# Display50_Cape.net
KiCad netlist of a schematic drawn in EAGLE
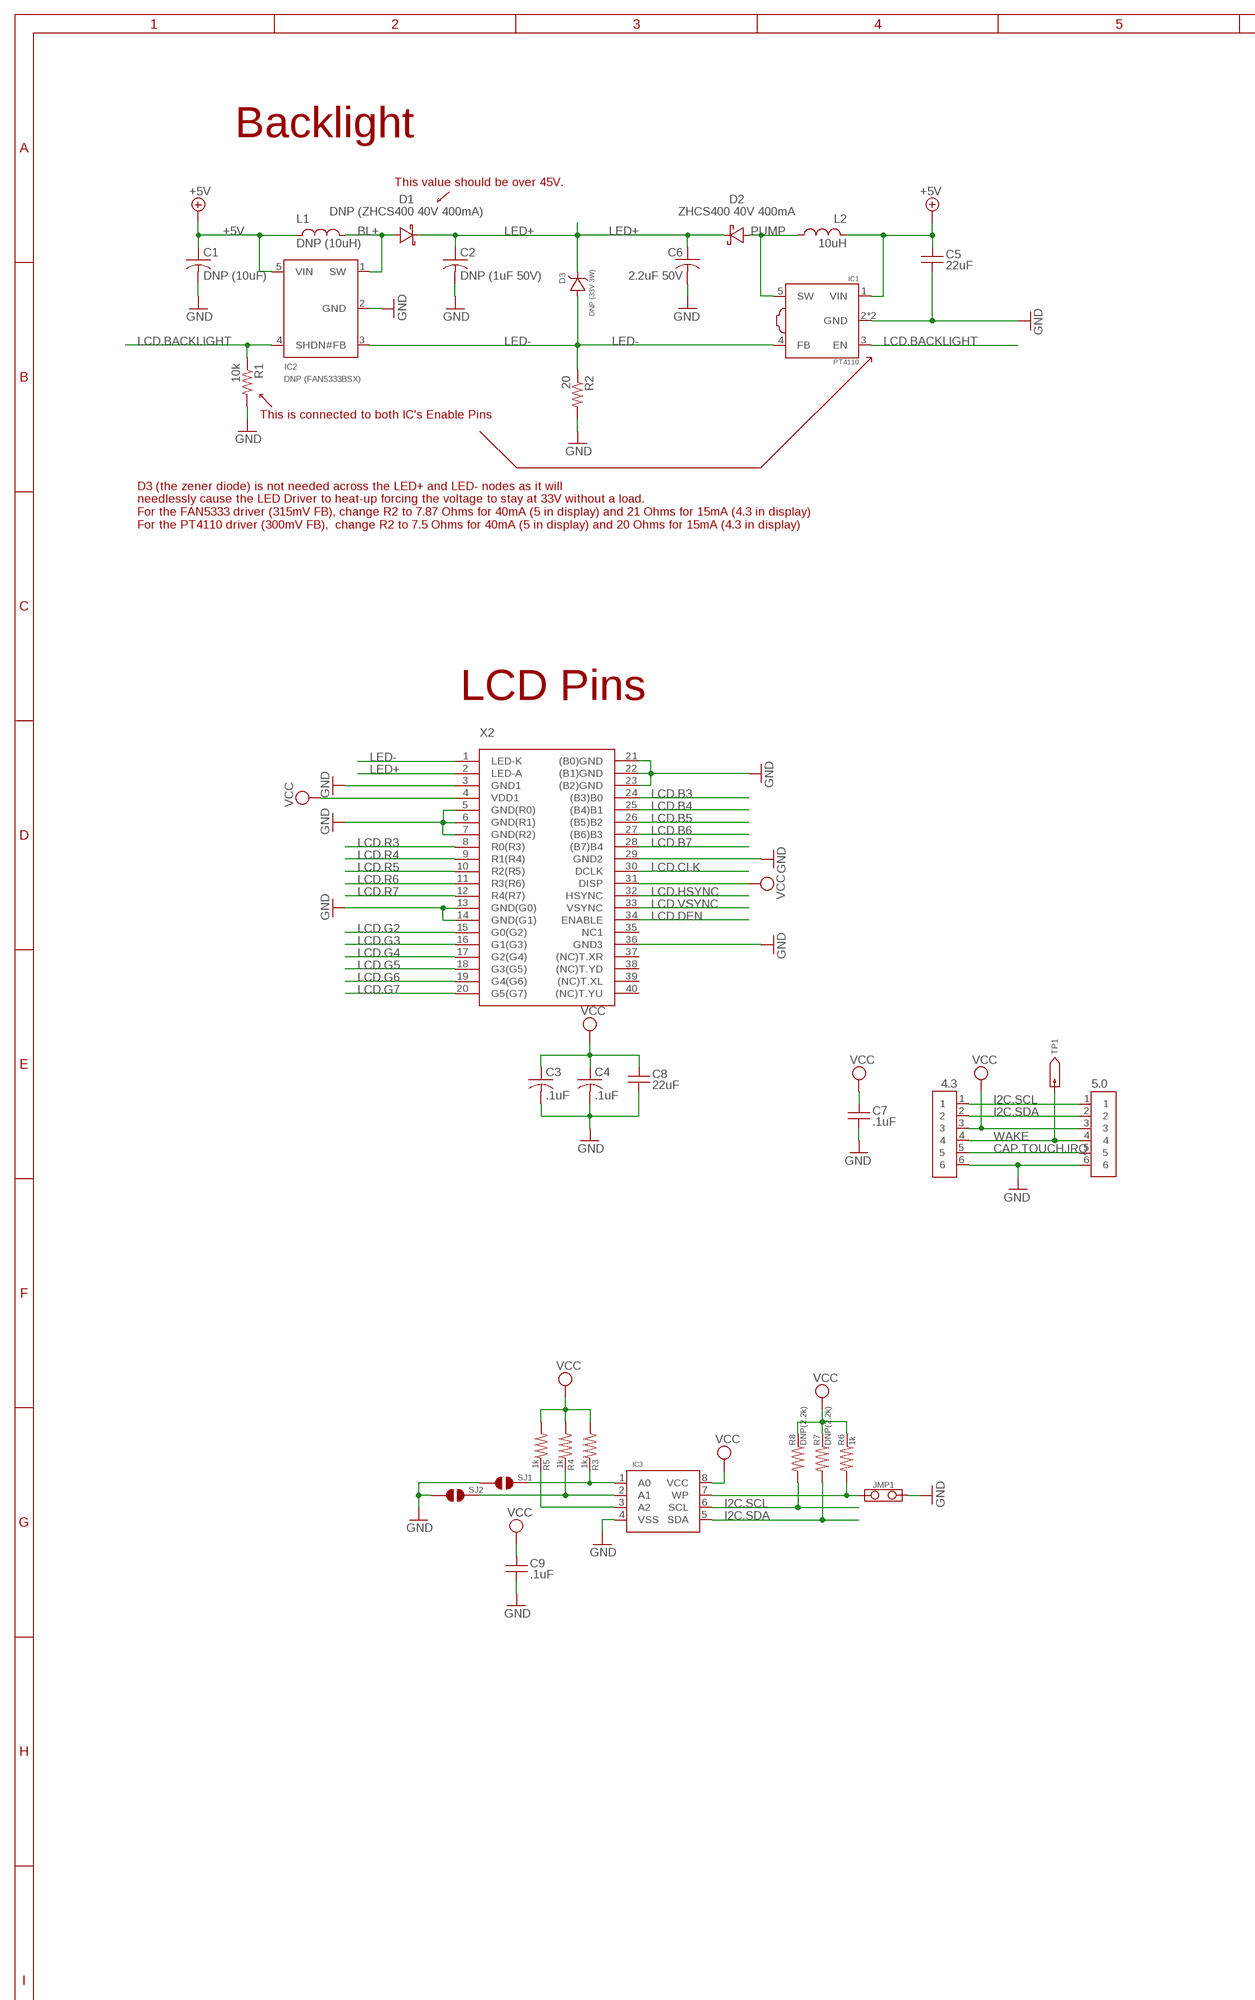
[diagram p0: schematic, sheet 1, part 1 of 2]
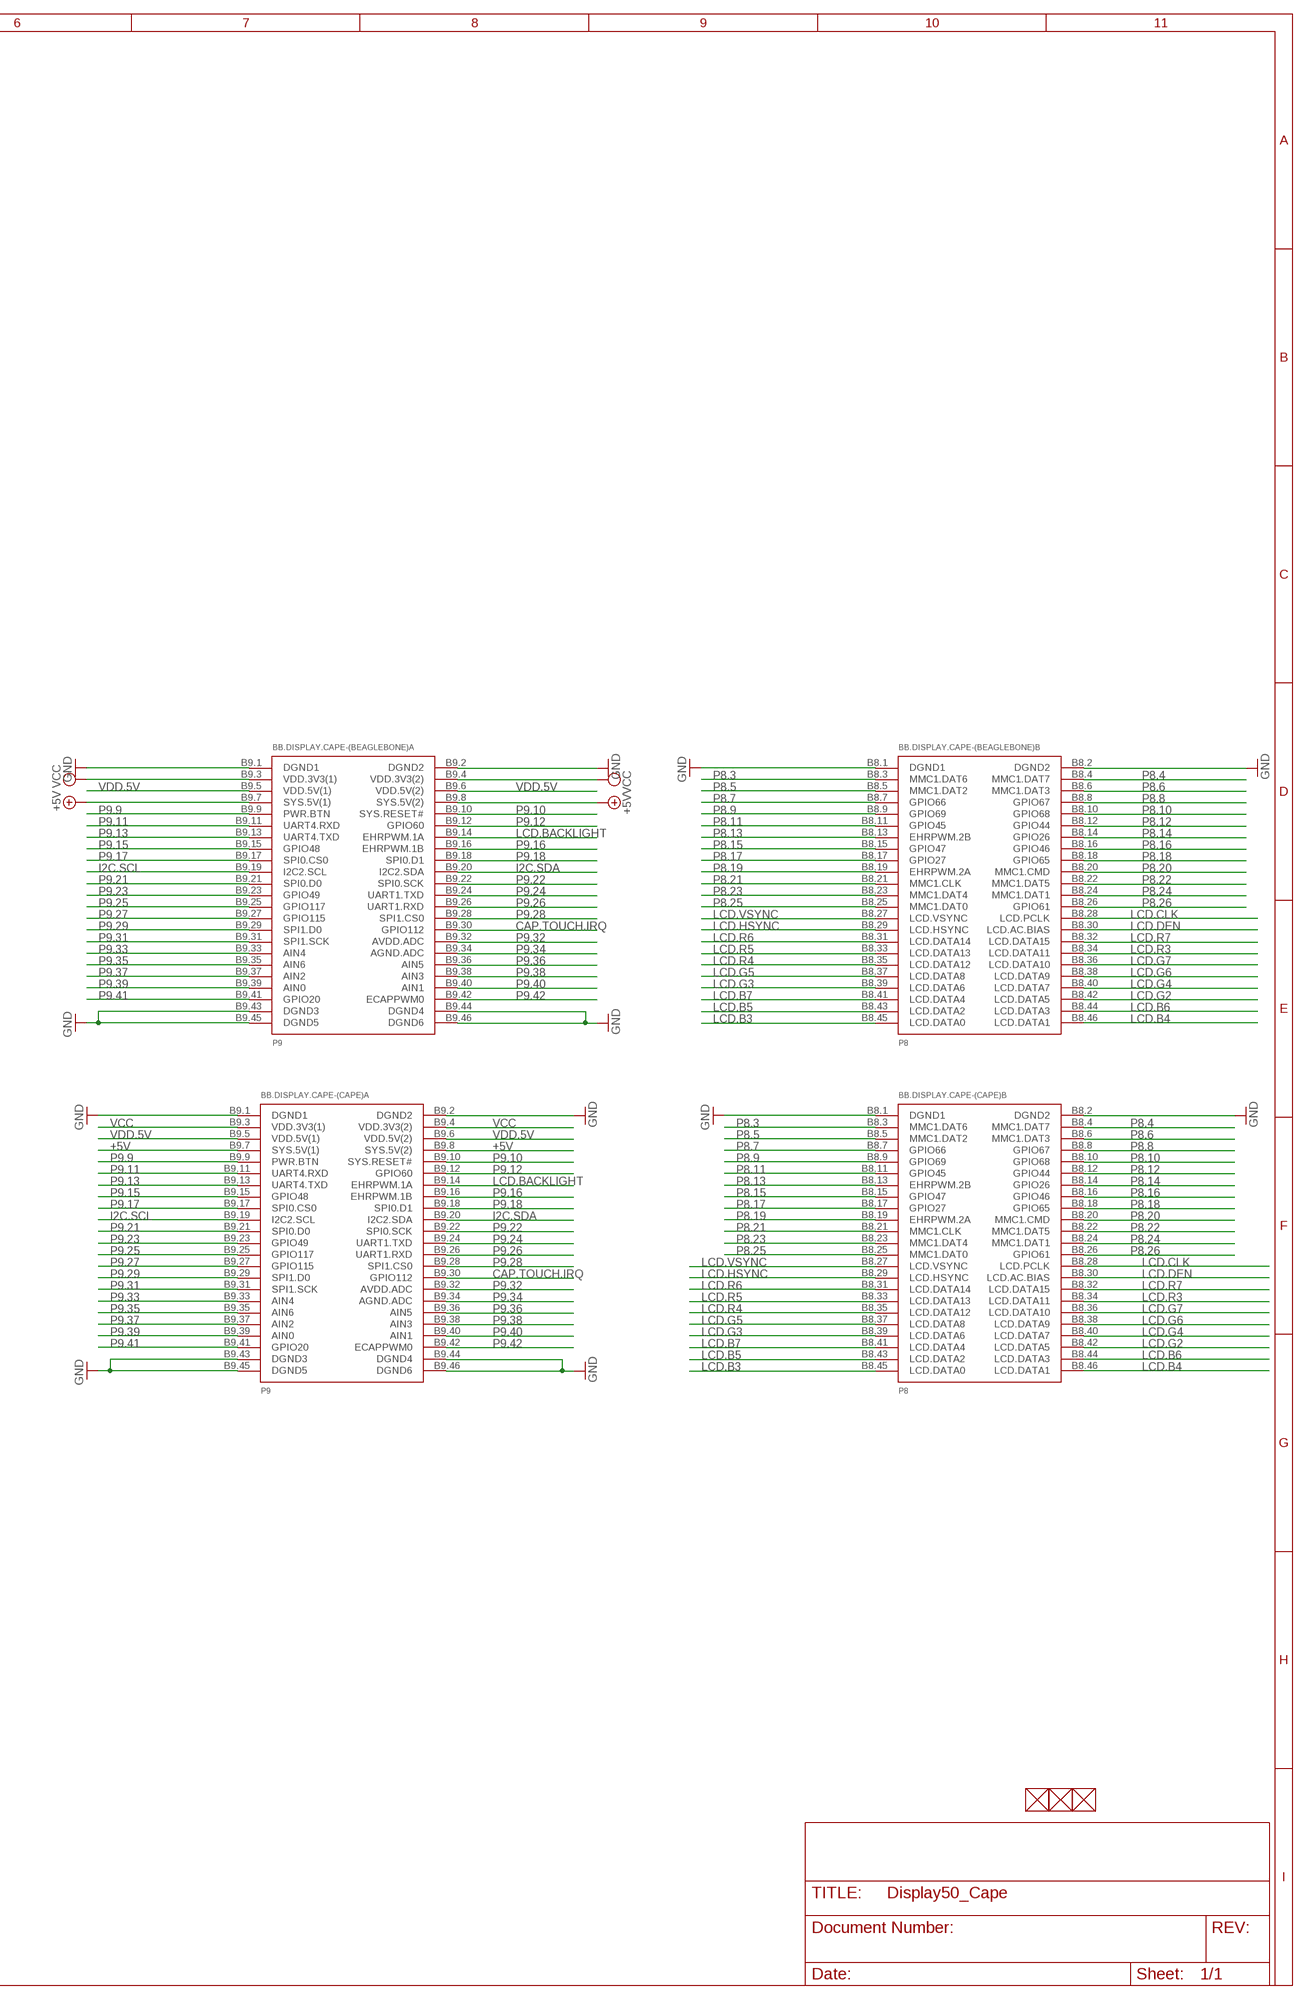
[diagram p1: schematic, sheet 1, part 2 of 2]

(export (version "E")
  (design (tool "Eeschema 10.0.6"))
  (components
    (comp (ref "4.3")
      (value "6-PIN-(0.5MM-PITCH)-FPC-CONNECTOR")
      (footprint "eagle-import:6-PIN-(0.5MM-PITCH)-FPC-CONNECTOR")
      (libsource (lib "eagle-import") (part "6-PIN-(0.5MM-PITCH)-FPC-CONNECTOR"))
    )
    (comp (ref "5.0")
      (value "6-PIN-(0.5MM-PITCH)-FPC-CONNECTOR")
      (footprint "eagle-import:6-PIN-(0.5MM-PITCH)-FPC-CONNECTOR")
      (libsource (lib "eagle-import") (part "6-PIN-(0.5MM-PITCH)-FPC-CONNECTOR"))
    )
    (comp (ref "BB.DISPLAY.CAPE-(BEAGLEBONE)")
      (value "BEAGLEBONE.CAPE.DISPLAY-X.BEAGLEBONE")
      (footprint "eagle-import:BEAGLEBONE.CAPE.DISPLAY-X.BEAGLEBONE")
      (libsource (lib "eagle-import") (part "BEAGLEBONE.CAPE.DISPLAY-X.BEAGLEBONE"))
    )
    (comp (ref "BB.DISPLAY.CAPE-(CAPE)")
      (value "BEAGLEBONE.CAPE.DISPLAY-X.CAPE")
      (footprint "eagle-import:BEAGLEBONE.CAPE.DISPLAY-X.CAPE")
      (libsource (lib "eagle-import") (part "BEAGLEBONE.CAPE.DISPLAY-X.CAPE"))
    )
    (comp (ref "C1")
      (value "DNP (10uF)")
      (footprint "eagle-import:C0603K")
      (libsource (lib "eagle-import") (part "C-USC0603K"))
    )
    (comp (ref "C2")
      (value "DNP (1uF 50V)")
      (footprint "eagle-import:C0805K")
      (libsource (lib "eagle-import") (part "C-USC0805K"))
    )
    (comp (ref "C3")
      (value ".1uF")
      (footprint "eagle-import:C0402K")
      (libsource (lib "eagle-import") (part "C-USC0402K"))
    )
    (comp (ref "C4")
      (value ".1uF")
      (footprint "eagle-import:C0402K")
      (libsource (lib "eagle-import") (part "C-USC0402K"))
    )
    (comp (ref "C5")
      (value "22uF")
      (footprint "eagle-import:0805")
      (libsource (lib "eagle-import") (part "CAPACITOR-(INCH)-0805"))
    )
    (comp (ref "C6")
      (value "2.2uF 50V")
      (footprint "eagle-import:C0805K")
      (libsource (lib "eagle-import") (part "C-USC0805K"))
    )
    (comp (ref "C7")
      (value ".1uF")
      (footprint "eagle-import:0402")
      (libsource (lib "eagle-import") (part "CAPACITOR-(INCH)-0402"))
    )
    (comp (ref "C8")
      (value "22uF")
      (footprint "eagle-import:0805")
      (libsource (lib "eagle-import") (part "CAPACITOR-(INCH)-0805"))
    )
    (comp (ref "C9")
      (value ".1uF")
      (footprint "eagle-import:0402")
      (libsource (lib "eagle-import") (part "CAPACITOR-(INCH)-0402"))
    )
    (comp (ref "D1")
      (value "DNP (ZHCS400 40V 400mA)")
      (footprint "eagle-import:SOD323(NXP)WAVE")
      (libsource (lib "eagle-import") (part "DIODE-SCHOTTKY-(NXP)-SOD323-(WAVE)"))
    )
    (comp (ref "D2")
      (value "ZHCS400 40V 400mA")
      (footprint "eagle-import:SOD323(NXP)WAVE")
      (libsource (lib "eagle-import") (part "DIODE-SCHOTTKY-(NXP)-SOD323-(WAVE)"))
    )
    (comp (ref "D3")
      (value "DNP (33V 3W)")
      (footprint "eagle-import:SMB(ON.SEMI)")
      (libsource (lib "eagle-import") (part "DIODE-ZENER-"))
    )
    (comp (ref "FUD1")
      (value "FIDUCIAL")
      (footprint "eagle-import:FIDUCIAL_40MIL")
      (libsource (lib "eagle-import") (part "FIDUCIAL"))
    )
    (comp (ref "FUD2")
      (value "FIDUCIAL")
      (footprint "eagle-import:FIDUCIAL_40MIL")
      (libsource (lib "eagle-import") (part "FIDUCIAL"))
    )
    (comp (ref "FUD3")
      (value "FIDUCIAL")
      (footprint "eagle-import:FIDUCIAL_40MIL")
      (libsource (lib "eagle-import") (part "FIDUCIAL"))
    )
    (comp (ref "IC1")
      (value "PT4110")
      (footprint "eagle-import:SOT89-5(DIODES)")
      (libsource (lib "eagle-import") (part "PT4110"))
    )
    (comp (ref "IC2")
      (value "DNP (FAN5333BSX)")
      (footprint "eagle-import:SOT23-5(FAIRCHILD)")
      (libsource (lib "eagle-import") (part "FAN533X"))
    )
    (comp (ref "IC3")
      (value "CAT24C32")
      (footprint "eagle-import:UDFN8,2X3(ON-SEMI)")
      (libsource (lib "eagle-import") (part "CAT24C32"))
    )
    (comp (ref "JMP1")
      (value "JUMPER-(X2)")
      (footprint "eagle-import:JUMPER-(X2)")
      (libsource (lib "eagle-import") (part "JUMPER-(X2)"))
    )
    (comp (ref "L1")
      (value "DNP (10uH)")
      (footprint "eagle-import:NRS(TAIYO.YUDEN)")
      (libsource (lib "eagle-import") (part "INDUCTOR-(TAIYO-YUDEN)-NRS5030"))
    )
    (comp (ref "L2")
      (value "10uH")
      (footprint "eagle-import:NRS(TAIYO.YUDEN)")
      (libsource (lib "eagle-import") (part "INDUCTOR-(TAIYO-YUDEN)-NRS5030"))
    )
    (comp (ref "R1")
      (value "10k")
      (footprint "eagle-import:R0603")
      (libsource (lib "eagle-import") (part "R-US_R0603"))
    )
    (comp (ref "R2")
      (value "20")
      (footprint "eagle-import:R0603")
      (libsource (lib "eagle-import") (part "R-US_R0603"))
    )
    (comp (ref "R3")
      (value "1k")
      (footprint "eagle-import:0402")
      (libsource (lib "eagle-import") (part "RESISTOR-(INCH)-0402"))
    )
    (comp (ref "R4")
      (value "1k")
      (footprint "eagle-import:0402")
      (libsource (lib "eagle-import") (part "RESISTOR-(INCH)-0402"))
    )
    (comp (ref "R5")
      (value "1k")
      (footprint "eagle-import:0402")
      (libsource (lib "eagle-import") (part "RESISTOR-(INCH)-0402"))
    )
    (comp (ref "R6")
      (value "1k")
      (footprint "eagle-import:0402")
      (libsource (lib "eagle-import") (part "RESISTOR-(INCH)-0402"))
    )
    (comp (ref "R7")
      (value "DNP(2.2k)")
      (footprint "eagle-import:0402")
      (libsource (lib "eagle-import") (part "RESISTOR-(INCH)-0402"))
    )
    (comp (ref "R8")
      (value "DNP(2.2k)")
      (footprint "eagle-import:0402")
      (libsource (lib "eagle-import") (part "RESISTOR-(INCH)-0402"))
    )
    (comp (ref "SJ1")
      (value "SOLDER.JOINT-(INCH)-0402")
      (footprint "eagle-import:SOLDER.JOINT(0402)")
      (libsource (lib "eagle-import") (part "SOLDER.JOINT-(INCH)-0402"))
    )
    (comp (ref "SJ2")
      (value "SOLDER.JOINT-(INCH)-0402")
      (footprint "eagle-import:SOLDER.JOINT(0402)")
      (libsource (lib "eagle-import") (part "SOLDER.JOINT-(INCH)-0402"))
    )
    (comp (ref "TP1")
      (value "TESTPAD/W_HOLE_1X1")
      (footprint "eagle-import:TESTPAD_W_HOLE_1X1")
      (libsource (lib "eagle-import") (part "TESTPAD/W_HOLE_1X1"))
    )
    (comp (ref "X2")
      (value "LCD-40PIN_FFC/FPC_0.5MM_PITCH")
      (footprint "eagle-import:KISD04-40_T1_E")
      (libsource (lib "eagle-import") (part "LCD-40PIN_FFC/FPC_0.5MM_PITCH"))
    )
  )
  (nets
    (net (code "1") (name "+5V") (class "Default")
      (node (ref "BB.DISPLAY.CAPE-(BEAGLEBONE)") (pin "B9.7") (pinfunction "SYS.5V(1)_B9.7") (pintype "bidirectional"))
      (node (ref "BB.DISPLAY.CAPE-(BEAGLEBONE)") (pin "B9.8") (pinfunction "SYS.5V(2)_B9.8") (pintype "bidirectional"))
      (node (ref "BB.DISPLAY.CAPE-(CAPE)") (pin "B9.7") (pinfunction "SYS.5V(1)_B9.7") (pintype "bidirectional"))
      (node (ref "BB.DISPLAY.CAPE-(CAPE)") (pin "B9.8") (pinfunction "SYS.5V(2)_B9.8") (pintype "bidirectional"))
      (node (ref "C1") (pin "1") (pinfunction "1_1") (pintype "passive"))
      (node (ref "C5") (pin "1") (pinfunction "1_1") (pintype "bidirectional"))
      (node (ref "IC1") (pin "1") (pinfunction "VIN_1") (pintype "bidirectional"))
      (node (ref "IC2") (pin "5") (pinfunction "VIN_5") (pintype "bidirectional"))
      (node (ref "L1") (pin "1") (pinfunction "1_1") (pintype "bidirectional"))
      (node (ref "L2") (pin "1") (pinfunction "1_1") (pintype "bidirectional"))
    )
    (net (code "2") (name "/BL+") (class "Default")
      (node (ref "D1") (pin "A") (pinfunction "ANODE_A") (pintype "bidirectional"))
      (node (ref "IC2") (pin "1") (pinfunction "SW_1") (pintype "bidirectional"))
      (node (ref "L1") (pin "2") (pinfunction "2_2") (pintype "bidirectional"))
    )
    (net (code "3") (name "/CAP.TOUCH.IRQ") (class "Default")
      (node (ref "4.3") (pin "5") (pinfunction "5_5") (pintype "bidirectional"))
      (node (ref "5.0") (pin "5") (pinfunction "5_5") (pintype "bidirectional"))
      (node (ref "BB.DISPLAY.CAPE-(BEAGLEBONE)") (pin "B9.30") (pinfunction "GPIO112_B9.30") (pintype "bidirectional"))
      (node (ref "BB.DISPLAY.CAPE-(CAPE)") (pin "B9.30") (pinfunction "GPIO112_B9.30") (pintype "bidirectional"))
    )
    (net (code "4") (name "/I2C.SCL") (class "Default")
      (node (ref "4.3") (pin "1") (pinfunction "1_1") (pintype "bidirectional"))
      (node (ref "5.0") (pin "1") (pinfunction "1_1") (pintype "bidirectional"))
      (node (ref "BB.DISPLAY.CAPE-(BEAGLEBONE)") (pin "B9.19") (pinfunction "I2C2.SCL_B9.19") (pintype "bidirectional"))
      (node (ref "BB.DISPLAY.CAPE-(CAPE)") (pin "B9.19") (pinfunction "I2C2.SCL_B9.19") (pintype "bidirectional"))
      (node (ref "IC3") (pin "6") (pinfunction "SCL_6") (pintype "bidirectional"))
      (node (ref "R8") (pin "1") (pinfunction "1_1") (pintype "bidirectional"))
    )
    (net (code "5") (name "/I2C.SDA") (class "Default")
      (node (ref "4.3") (pin "2") (pinfunction "2_2") (pintype "bidirectional"))
      (node (ref "5.0") (pin "2") (pinfunction "2_2") (pintype "bidirectional"))
      (node (ref "BB.DISPLAY.CAPE-(BEAGLEBONE)") (pin "B9.20") (pinfunction "I2C2.SDA_B9.20") (pintype "bidirectional"))
      (node (ref "BB.DISPLAY.CAPE-(CAPE)") (pin "B9.20") (pinfunction "I2C2.SDA_B9.20") (pintype "bidirectional"))
      (node (ref "IC3") (pin "5") (pinfunction "SDA_5") (pintype "bidirectional"))
      (node (ref "R7") (pin "1") (pinfunction "1_1") (pintype "bidirectional"))
    )
    (net (code "6") (name "/LCD.B3") (class "Default")
      (node (ref "BB.DISPLAY.CAPE-(BEAGLEBONE)") (pin "B8.45") (pinfunction "LCD.DATA0_B8.45") (pintype "bidirectional"))
      (node (ref "BB.DISPLAY.CAPE-(CAPE)") (pin "B8.45") (pinfunction "LCD.DATA0_B8.45") (pintype "bidirectional"))
      (node (ref "X2") (pin "24") (pinfunction "(B3)B0_24") (pintype "bidirectional"))
    )
    (net (code "7") (name "/LCD.B4") (class "Default")
      (node (ref "BB.DISPLAY.CAPE-(BEAGLEBONE)") (pin "B8.46") (pinfunction "LCD.DATA1_B8.46") (pintype "bidirectional"))
      (node (ref "BB.DISPLAY.CAPE-(CAPE)") (pin "B8.46") (pinfunction "LCD.DATA1_B8.46") (pintype "bidirectional"))
      (node (ref "X2") (pin "25") (pinfunction "(B4)B1_25") (pintype "bidirectional"))
    )
    (net (code "8") (name "/LCD.B5") (class "Default")
      (node (ref "BB.DISPLAY.CAPE-(BEAGLEBONE)") (pin "B8.43") (pinfunction "LCD.DATA2_B8.43") (pintype "bidirectional"))
      (node (ref "BB.DISPLAY.CAPE-(CAPE)") (pin "B8.43") (pinfunction "LCD.DATA2_B8.43") (pintype "bidirectional"))
      (node (ref "X2") (pin "26") (pinfunction "(B5)B2_26") (pintype "bidirectional"))
    )
    (net (code "9") (name "/LCD.B6") (class "Default")
      (node (ref "BB.DISPLAY.CAPE-(BEAGLEBONE)") (pin "B8.44") (pinfunction "LCD.DATA3_B8.44") (pintype "bidirectional"))
      (node (ref "BB.DISPLAY.CAPE-(CAPE)") (pin "B8.44") (pinfunction "LCD.DATA3_B8.44") (pintype "bidirectional"))
      (node (ref "X2") (pin "27") (pinfunction "(B6)B3_27") (pintype "bidirectional"))
    )
    (net (code "10") (name "/LCD.B7") (class "Default")
      (node (ref "BB.DISPLAY.CAPE-(BEAGLEBONE)") (pin "B8.41") (pinfunction "LCD.DATA4_B8.41") (pintype "bidirectional"))
      (node (ref "BB.DISPLAY.CAPE-(CAPE)") (pin "B8.41") (pinfunction "LCD.DATA4_B8.41") (pintype "bidirectional"))
      (node (ref "X2") (pin "28") (pinfunction "(B7)B4_28") (pintype "bidirectional"))
    )
    (net (code "11") (name "/LCD.BACKLIGHT") (class "Default")
      (node (ref "BB.DISPLAY.CAPE-(BEAGLEBONE)") (pin "B9.14") (pinfunction "EHRPWM.1A_B9.14") (pintype "bidirectional"))
      (node (ref "BB.DISPLAY.CAPE-(CAPE)") (pin "B9.14") (pinfunction "EHRPWM.1A_B9.14") (pintype "bidirectional"))
      (node (ref "IC1") (pin "3") (pinfunction "EN_3") (pintype "bidirectional"))
      (node (ref "IC2") (pin "4") (pinfunction "SHDN#_4") (pintype "bidirectional"))
      (node (ref "R1") (pin "1") (pinfunction "1_1") (pintype "passive"))
    )
    (net (code "12") (name "/LCD.CLK") (class "Default")
      (node (ref "BB.DISPLAY.CAPE-(BEAGLEBONE)") (pin "B8.28") (pinfunction "LCD.PCLK_B8.28") (pintype "bidirectional"))
      (node (ref "BB.DISPLAY.CAPE-(CAPE)") (pin "B8.28") (pinfunction "LCD.PCLK_B8.28") (pintype "bidirectional"))
      (node (ref "X2") (pin "30") (pinfunction "DCLK_30") (pintype "bidirectional"))
    )
    (net (code "13") (name "/LCD.DEN") (class "Default")
      (node (ref "BB.DISPLAY.CAPE-(BEAGLEBONE)") (pin "B8.30") (pinfunction "LCD.AC.BIAS_B8.30") (pintype "bidirectional"))
      (node (ref "BB.DISPLAY.CAPE-(CAPE)") (pin "B8.30") (pinfunction "LCD.AC.BIAS_B8.30") (pintype "bidirectional"))
      (node (ref "X2") (pin "34") (pinfunction "ENABLE_34") (pintype "bidirectional"))
    )
    (net (code "14") (name "/LCD.G2") (class "Default")
      (node (ref "BB.DISPLAY.CAPE-(BEAGLEBONE)") (pin "B8.42") (pinfunction "LCD.DATA5_B8.42") (pintype "bidirectional"))
      (node (ref "BB.DISPLAY.CAPE-(CAPE)") (pin "B8.42") (pinfunction "LCD.DATA5_B8.42") (pintype "bidirectional"))
      (node (ref "X2") (pin "15") (pinfunction "G0(G2)_15") (pintype "bidirectional"))
    )
    (net (code "15") (name "/LCD.G3") (class "Default")
      (node (ref "BB.DISPLAY.CAPE-(BEAGLEBONE)") (pin "B8.39") (pinfunction "LCD.DATA6_B8.39") (pintype "bidirectional"))
      (node (ref "BB.DISPLAY.CAPE-(CAPE)") (pin "B8.39") (pinfunction "LCD.DATA6_B8.39") (pintype "bidirectional"))
      (node (ref "X2") (pin "16") (pinfunction "G1(G3)_16") (pintype "bidirectional"))
    )
    (net (code "16") (name "/LCD.G4") (class "Default")
      (node (ref "BB.DISPLAY.CAPE-(BEAGLEBONE)") (pin "B8.40") (pinfunction "LCD.DATA7_B8.40") (pintype "bidirectional"))
      (node (ref "BB.DISPLAY.CAPE-(CAPE)") (pin "B8.40") (pinfunction "LCD.DATA7_B8.40") (pintype "bidirectional"))
      (node (ref "X2") (pin "17") (pinfunction "G2(G4)_17") (pintype "bidirectional"))
    )
    (net (code "17") (name "/LCD.G5") (class "Default")
      (node (ref "BB.DISPLAY.CAPE-(BEAGLEBONE)") (pin "B8.37") (pinfunction "LCD.DATA8_B8.37") (pintype "bidirectional"))
      (node (ref "BB.DISPLAY.CAPE-(CAPE)") (pin "B8.37") (pinfunction "LCD.DATA8_B8.37") (pintype "bidirectional"))
      (node (ref "X2") (pin "18") (pinfunction "G3(G5)_18") (pintype "bidirectional"))
    )
    (net (code "18") (name "/LCD.G6") (class "Default")
      (node (ref "BB.DISPLAY.CAPE-(BEAGLEBONE)") (pin "B8.38") (pinfunction "LCD.DATA9_B8.38") (pintype "bidirectional"))
      (node (ref "BB.DISPLAY.CAPE-(CAPE)") (pin "B8.38") (pinfunction "LCD.DATA9_B8.38") (pintype "bidirectional"))
      (node (ref "X2") (pin "19") (pinfunction "G4(G6)_19") (pintype "bidirectional"))
    )
    (net (code "19") (name "/LCD.G7") (class "Default")
      (node (ref "BB.DISPLAY.CAPE-(BEAGLEBONE)") (pin "B8.36") (pinfunction "LCD.DATA10_B8.36") (pintype "bidirectional"))
      (node (ref "BB.DISPLAY.CAPE-(CAPE)") (pin "B8.36") (pinfunction "LCD.DATA10_B8.36") (pintype "bidirectional"))
      (node (ref "X2") (pin "20") (pinfunction "G5(G7)_20") (pintype "bidirectional"))
    )
    (net (code "20") (name "/LCD.HSYNC") (class "Default")
      (node (ref "BB.DISPLAY.CAPE-(BEAGLEBONE)") (pin "B8.29") (pinfunction "LCD.HSYNC_B8.29") (pintype "bidirectional"))
      (node (ref "BB.DISPLAY.CAPE-(CAPE)") (pin "B8.29") (pinfunction "LCD.HSYNC_B8.29") (pintype "bidirectional"))
      (node (ref "X2") (pin "32") (pinfunction "HSYNC_32") (pintype "bidirectional"))
    )
    (net (code "21") (name "/LCD.R3") (class "Default")
      (node (ref "BB.DISPLAY.CAPE-(BEAGLEBONE)") (pin "B8.34") (pinfunction "LCD.DATA11_B8.34") (pintype "bidirectional"))
      (node (ref "BB.DISPLAY.CAPE-(CAPE)") (pin "B8.34") (pinfunction "LCD.DATA11_B8.34") (pintype "bidirectional"))
      (node (ref "X2") (pin "8") (pinfunction "R0(R3)_8") (pintype "bidirectional"))
    )
    (net (code "22") (name "/LCD.R4") (class "Default")
      (node (ref "BB.DISPLAY.CAPE-(BEAGLEBONE)") (pin "B8.35") (pinfunction "LCD.DATA12_B8.35") (pintype "bidirectional"))
      (node (ref "BB.DISPLAY.CAPE-(CAPE)") (pin "B8.35") (pinfunction "LCD.DATA12_B8.35") (pintype "bidirectional"))
      (node (ref "X2") (pin "9") (pinfunction "R1(R4)_9") (pintype "bidirectional"))
    )
    (net (code "23") (name "/LCD.R5") (class "Default")
      (node (ref "BB.DISPLAY.CAPE-(BEAGLEBONE)") (pin "B8.33") (pinfunction "LCD.DATA13_B8.33") (pintype "bidirectional"))
      (node (ref "BB.DISPLAY.CAPE-(CAPE)") (pin "B8.33") (pinfunction "LCD.DATA13_B8.33") (pintype "bidirectional"))
      (node (ref "X2") (pin "10") (pinfunction "R2(R5)_10") (pintype "bidirectional"))
    )
    (net (code "24") (name "/LCD.R6") (class "Default")
      (node (ref "BB.DISPLAY.CAPE-(BEAGLEBONE)") (pin "B8.31") (pinfunction "LCD.DATA14_B8.31") (pintype "bidirectional"))
      (node (ref "BB.DISPLAY.CAPE-(CAPE)") (pin "B8.31") (pinfunction "LCD.DATA14_B8.31") (pintype "bidirectional"))
      (node (ref "X2") (pin "11") (pinfunction "R3(R6)_11") (pintype "bidirectional"))
    )
    (net (code "25") (name "/LCD.R7") (class "Default")
      (node (ref "BB.DISPLAY.CAPE-(BEAGLEBONE)") (pin "B8.32") (pinfunction "LCD.DATA15_B8.32") (pintype "bidirectional"))
      (node (ref "BB.DISPLAY.CAPE-(CAPE)") (pin "B8.32") (pinfunction "LCD.DATA15_B8.32") (pintype "bidirectional"))
      (node (ref "X2") (pin "12") (pinfunction "R4(R7)_12") (pintype "bidirectional"))
    )
    (net (code "26") (name "/LCD.VSYNC") (class "Default")
      (node (ref "BB.DISPLAY.CAPE-(BEAGLEBONE)") (pin "B8.27") (pinfunction "LCD.VSYNC_B8.27") (pintype "bidirectional"))
      (node (ref "BB.DISPLAY.CAPE-(CAPE)") (pin "B8.27") (pinfunction "LCD.VSYNC_B8.27") (pintype "bidirectional"))
      (node (ref "X2") (pin "33") (pinfunction "VSYNC_33") (pintype "bidirectional"))
    )
    (net (code "27") (name "/LED+") (class "Default")
      (node (ref "C2") (pin "1") (pinfunction "1_1") (pintype "passive"))
      (node (ref "C6") (pin "1") (pinfunction "1_1") (pintype "passive"))
      (node (ref "D1") (pin "C") (pinfunction "CATHODE_C") (pintype "bidirectional"))
      (node (ref "D2") (pin "C") (pinfunction "CATHODE_C") (pintype "bidirectional"))
      (node (ref "D3") (pin "K") (pinfunction "K_K") (pintype "bidirectional"))
      (node (ref "X2") (pin "2") (pinfunction "LED-A_2") (pintype "bidirectional"))
    )
    (net (code "28") (name "/LED-") (class "Default")
      (node (ref "D3") (pin "A") (pinfunction "A_A") (pintype "bidirectional"))
      (node (ref "IC1") (pin "4") (pinfunction "FB_4") (pintype "bidirectional"))
      (node (ref "IC2") (pin "3") (pinfunction "FB_3") (pintype "bidirectional"))
      (node (ref "R2") (pin "1") (pinfunction "1_1") (pintype "passive"))
      (node (ref "X2") (pin "1") (pinfunction "LED-K_1") (pintype "bidirectional"))
    )
    (net (code "29") (name "/P8.3") (class "Default")
      (node (ref "BB.DISPLAY.CAPE-(BEAGLEBONE)") (pin "B8.3") (pinfunction "MMC1.DAT6_B8.3") (pintype "bidirectional"))
      (node (ref "BB.DISPLAY.CAPE-(CAPE)") (pin "B8.3") (pinfunction "MMC1.DAT6_B8.3") (pintype "bidirectional"))
    )
    (net (code "30") (name "/P8.4") (class "Default")
      (node (ref "BB.DISPLAY.CAPE-(BEAGLEBONE)") (pin "B8.4") (pinfunction "MMC1.DAT7_B8.4") (pintype "bidirectional"))
      (node (ref "BB.DISPLAY.CAPE-(CAPE)") (pin "B8.4") (pinfunction "MMC1.DAT7_B8.4") (pintype "bidirectional"))
    )
    (net (code "31") (name "/P8.5") (class "Default")
      (node (ref "BB.DISPLAY.CAPE-(BEAGLEBONE)") (pin "B8.5") (pinfunction "MMC1.DAT2_B8.5") (pintype "bidirectional"))
      (node (ref "BB.DISPLAY.CAPE-(CAPE)") (pin "B8.5") (pinfunction "MMC1.DAT2_B8.5") (pintype "bidirectional"))
    )
    (net (code "32") (name "/P8.6") (class "Default")
      (node (ref "BB.DISPLAY.CAPE-(BEAGLEBONE)") (pin "B8.6") (pinfunction "MMC1.DAT3_B8.6") (pintype "bidirectional"))
      (node (ref "BB.DISPLAY.CAPE-(CAPE)") (pin "B8.6") (pinfunction "MMC1.DAT3_B8.6") (pintype "bidirectional"))
    )
    (net (code "33") (name "/P8.7") (class "Default")
      (node (ref "BB.DISPLAY.CAPE-(BEAGLEBONE)") (pin "B8.7") (pinfunction "GPIO66_B8.7") (pintype "bidirectional"))
      (node (ref "BB.DISPLAY.CAPE-(CAPE)") (pin "B8.7") (pinfunction "GPIO66_B8.7") (pintype "bidirectional"))
    )
    (net (code "34") (name "/P8.8") (class "Default")
      (node (ref "BB.DISPLAY.CAPE-(BEAGLEBONE)") (pin "B8.8") (pinfunction "GPIO67_B8.8") (pintype "bidirectional"))
      (node (ref "BB.DISPLAY.CAPE-(CAPE)") (pin "B8.8") (pinfunction "GPIO67_B8.8") (pintype "bidirectional"))
    )
    (net (code "35") (name "/P8.9") (class "Default")
      (node (ref "BB.DISPLAY.CAPE-(BEAGLEBONE)") (pin "B8.9") (pinfunction "GPIO69_B8.9") (pintype "bidirectional"))
      (node (ref "BB.DISPLAY.CAPE-(CAPE)") (pin "B8.9") (pinfunction "GPIO69_B8.9") (pintype "bidirectional"))
    )
    (net (code "36") (name "/P8.10") (class "Default")
      (node (ref "BB.DISPLAY.CAPE-(BEAGLEBONE)") (pin "B8.10") (pinfunction "GPIO68_B8.10") (pintype "bidirectional"))
      (node (ref "BB.DISPLAY.CAPE-(CAPE)") (pin "B8.10") (pinfunction "GPIO68_B8.10") (pintype "bidirectional"))
    )
    (net (code "37") (name "/P8.11") (class "Default")
      (node (ref "BB.DISPLAY.CAPE-(BEAGLEBONE)") (pin "B8.11") (pinfunction "GPIO45_B8.11") (pintype "bidirectional"))
      (node (ref "BB.DISPLAY.CAPE-(CAPE)") (pin "B8.11") (pinfunction "GPIO45_B8.11") (pintype "bidirectional"))
    )
    (net (code "38") (name "/P8.12") (class "Default")
      (node (ref "BB.DISPLAY.CAPE-(BEAGLEBONE)") (pin "B8.12") (pinfunction "GPIO44_B8.12") (pintype "bidirectional"))
      (node (ref "BB.DISPLAY.CAPE-(CAPE)") (pin "B8.12") (pinfunction "GPIO44_B8.12") (pintype "bidirectional"))
    )
    (net (code "39") (name "/P8.13") (class "Default")
      (node (ref "BB.DISPLAY.CAPE-(BEAGLEBONE)") (pin "B8.13") (pinfunction "EHRPWM.2B_B8.13") (pintype "bidirectional"))
      (node (ref "BB.DISPLAY.CAPE-(CAPE)") (pin "B8.13") (pinfunction "EHRPWM.2B_B8.13") (pintype "bidirectional"))
    )
    (net (code "40") (name "/P8.14") (class "Default")
      (node (ref "BB.DISPLAY.CAPE-(BEAGLEBONE)") (pin "B8.14") (pinfunction "GPIO26_B8.14") (pintype "bidirectional"))
      (node (ref "BB.DISPLAY.CAPE-(CAPE)") (pin "B8.14") (pinfunction "GPIO26_B8.14") (pintype "bidirectional"))
    )
    (net (code "41") (name "/P8.15") (class "Default")
      (node (ref "BB.DISPLAY.CAPE-(BEAGLEBONE)") (pin "B8.15") (pinfunction "GPIO47_B8.15") (pintype "bidirectional"))
      (node (ref "BB.DISPLAY.CAPE-(CAPE)") (pin "B8.15") (pinfunction "GPIO47_B8.15") (pintype "bidirectional"))
    )
    (net (code "42") (name "/P8.16") (class "Default")
      (node (ref "BB.DISPLAY.CAPE-(BEAGLEBONE)") (pin "B8.16") (pinfunction "GPIO46_B8.16") (pintype "bidirectional"))
      (node (ref "BB.DISPLAY.CAPE-(CAPE)") (pin "B8.16") (pinfunction "GPIO46_B8.16") (pintype "bidirectional"))
    )
    (net (code "43") (name "/P8.17") (class "Default")
      (node (ref "BB.DISPLAY.CAPE-(BEAGLEBONE)") (pin "B8.17") (pinfunction "GPIO27_B8.17") (pintype "bidirectional"))
      (node (ref "BB.DISPLAY.CAPE-(CAPE)") (pin "B8.17") (pinfunction "GPIO27_B8.17") (pintype "bidirectional"))
    )
    (net (code "44") (name "/P8.18") (class "Default")
      (node (ref "BB.DISPLAY.CAPE-(BEAGLEBONE)") (pin "B8.18") (pinfunction "GPIO65_B8.18") (pintype "bidirectional"))
      (node (ref "BB.DISPLAY.CAPE-(CAPE)") (pin "B8.18") (pinfunction "GPIO65_B8.18") (pintype "bidirectional"))
    )
    (net (code "45") (name "/P8.19") (class "Default")
      (node (ref "BB.DISPLAY.CAPE-(BEAGLEBONE)") (pin "B8.19") (pinfunction "EHRPWM.2A_B8.19") (pintype "bidirectional"))
      (node (ref "BB.DISPLAY.CAPE-(CAPE)") (pin "B8.19") (pinfunction "EHRPWM.2A_B8.19") (pintype "bidirectional"))
    )
    (net (code "46") (name "/P8.20") (class "Default")
      (node (ref "BB.DISPLAY.CAPE-(BEAGLEBONE)") (pin "B8.20") (pinfunction "MMC1.CMD_B8.20") (pintype "bidirectional"))
      (node (ref "BB.DISPLAY.CAPE-(CAPE)") (pin "B8.20") (pinfunction "MMC1.CMD_B8.20") (pintype "bidirectional"))
    )
    (net (code "47") (name "/P8.21") (class "Default")
      (node (ref "BB.DISPLAY.CAPE-(BEAGLEBONE)") (pin "B8.21") (pinfunction "MMC1.CLK_B8.21") (pintype "bidirectional"))
      (node (ref "BB.DISPLAY.CAPE-(CAPE)") (pin "B8.21") (pinfunction "MMC1.CLK_B8.21") (pintype "bidirectional"))
    )
    (net (code "48") (name "/P8.22") (class "Default")
      (node (ref "BB.DISPLAY.CAPE-(BEAGLEBONE)") (pin "B8.22") (pinfunction "MMC1.DAT5_B8.22") (pintype "bidirectional"))
      (node (ref "BB.DISPLAY.CAPE-(CAPE)") (pin "B8.22") (pinfunction "MMC1.DAT5_B8.22") (pintype "bidirectional"))
    )
    (net (code "49") (name "/P8.23") (class "Default")
      (node (ref "BB.DISPLAY.CAPE-(BEAGLEBONE)") (pin "B8.23") (pinfunction "MMC1.DAT4_B8.23") (pintype "bidirectional"))
      (node (ref "BB.DISPLAY.CAPE-(CAPE)") (pin "B8.23") (pinfunction "MMC1.DAT4_B8.23") (pintype "bidirectional"))
    )
    (net (code "50") (name "/P8.24") (class "Default")
      (node (ref "BB.DISPLAY.CAPE-(BEAGLEBONE)") (pin "B8.24") (pinfunction "MMC1.DAT1_B8.24") (pintype "bidirectional"))
      (node (ref "BB.DISPLAY.CAPE-(CAPE)") (pin "B8.24") (pinfunction "MMC1.DAT1_B8.24") (pintype "bidirectional"))
    )
    (net (code "51") (name "/P8.25") (class "Default")
      (node (ref "BB.DISPLAY.CAPE-(BEAGLEBONE)") (pin "B8.25") (pinfunction "MMC1.DAT0_B8.25") (pintype "bidirectional"))
      (node (ref "BB.DISPLAY.CAPE-(CAPE)") (pin "B8.25") (pinfunction "MMC1.DAT0_B8.25") (pintype "bidirectional"))
    )
    (net (code "52") (name "/P8.26") (class "Default")
      (node (ref "BB.DISPLAY.CAPE-(BEAGLEBONE)") (pin "B8.26") (pinfunction "GPIO61_B8.26") (pintype "bidirectional"))
      (node (ref "BB.DISPLAY.CAPE-(CAPE)") (pin "B8.26") (pinfunction "GPIO61_B8.26") (pintype "bidirectional"))
    )
    (net (code "53") (name "/P9.9") (class "Default")
      (node (ref "BB.DISPLAY.CAPE-(BEAGLEBONE)") (pin "B9.9") (pinfunction "PWR.BTN_B9.9") (pintype "bidirectional"))
      (node (ref "BB.DISPLAY.CAPE-(CAPE)") (pin "B9.9") (pinfunction "PWR.BTN_B9.9") (pintype "bidirectional"))
    )
    (net (code "54") (name "/P9.10") (class "Default")
      (node (ref "BB.DISPLAY.CAPE-(BEAGLEBONE)") (pin "B9.10") (pinfunction "SYS.RESET#_B9.10") (pintype "bidirectional"))
      (node (ref "BB.DISPLAY.CAPE-(CAPE)") (pin "B9.10") (pinfunction "SYS.RESET#_B9.10") (pintype "bidirectional"))
    )
    (net (code "55") (name "/P9.11") (class "Default")
      (node (ref "BB.DISPLAY.CAPE-(BEAGLEBONE)") (pin "B9.11") (pinfunction "UART4.RXD_B9.11") (pintype "bidirectional"))
      (node (ref "BB.DISPLAY.CAPE-(CAPE)") (pin "B9.11") (pinfunction "UART4.RXD_B9.11") (pintype "bidirectional"))
    )
    (net (code "56") (name "/P9.12") (class "Default")
      (node (ref "BB.DISPLAY.CAPE-(BEAGLEBONE)") (pin "B9.12") (pinfunction "GPIO60_B9.12") (pintype "bidirectional"))
      (node (ref "BB.DISPLAY.CAPE-(CAPE)") (pin "B9.12") (pinfunction "GPIO60_B9.12") (pintype "bidirectional"))
    )
    (net (code "57") (name "/P9.13") (class "Default")
      (node (ref "BB.DISPLAY.CAPE-(BEAGLEBONE)") (pin "B9.13") (pinfunction "UART4.TXD_B9.13") (pintype "bidirectional"))
      (node (ref "BB.DISPLAY.CAPE-(CAPE)") (pin "B9.13") (pinfunction "UART4.TXD_B9.13") (pintype "bidirectional"))
    )
    (net (code "58") (name "/P9.15") (class "Default")
      (node (ref "BB.DISPLAY.CAPE-(BEAGLEBONE)") (pin "B9.15") (pinfunction "GPIO48_B9.15") (pintype "bidirectional"))
      (node (ref "BB.DISPLAY.CAPE-(CAPE)") (pin "B9.15") (pinfunction "GPIO48_B9.15") (pintype "bidirectional"))
    )
    (net (code "59") (name "/P9.16") (class "Default")
      (node (ref "BB.DISPLAY.CAPE-(BEAGLEBONE)") (pin "B9.16") (pinfunction "EHRPWM.1B_B9.16") (pintype "bidirectional"))
      (node (ref "BB.DISPLAY.CAPE-(CAPE)") (pin "B9.16") (pinfunction "EHRPWM.1B_B9.16") (pintype "bidirectional"))
    )
    (net (code "60") (name "/P9.17") (class "Default")
      (node (ref "BB.DISPLAY.CAPE-(BEAGLEBONE)") (pin "B9.17") (pinfunction "SPI0.CS0_B9.17") (pintype "bidirectional"))
      (node (ref "BB.DISPLAY.CAPE-(CAPE)") (pin "B9.17") (pinfunction "SPI0.CS0_B9.17") (pintype "bidirectional"))
    )
    (net (code "61") (name "/P9.18") (class "Default")
      (node (ref "BB.DISPLAY.CAPE-(BEAGLEBONE)") (pin "B9.18") (pinfunction "SPI0.D1_B9.18") (pintype "bidirectional"))
      (node (ref "BB.DISPLAY.CAPE-(CAPE)") (pin "B9.18") (pinfunction "SPI0.D1_B9.18") (pintype "bidirectional"))
    )
    (net (code "62") (name "/P9.21") (class "Default")
      (node (ref "BB.DISPLAY.CAPE-(BEAGLEBONE)") (pin "B9.21") (pinfunction "SPI0.D0_B9.21") (pintype "bidirectional"))
      (node (ref "BB.DISPLAY.CAPE-(CAPE)") (pin "B9.21") (pinfunction "SPI0.D0_B9.21") (pintype "bidirectional"))
    )
    (net (code "63") (name "/P9.22") (class "Default")
      (node (ref "BB.DISPLAY.CAPE-(BEAGLEBONE)") (pin "B9.22") (pinfunction "SPI0.SCK_B9.22") (pintype "bidirectional"))
      (node (ref "BB.DISPLAY.CAPE-(CAPE)") (pin "B9.22") (pinfunction "SPI0.SCK_B9.22") (pintype "bidirectional"))
    )
    (net (code "64") (name "/P9.23") (class "Default")
      (node (ref "BB.DISPLAY.CAPE-(BEAGLEBONE)") (pin "B9.23") (pinfunction "GPIO49_B9.23") (pintype "bidirectional"))
      (node (ref "BB.DISPLAY.CAPE-(CAPE)") (pin "B9.23") (pinfunction "GPIO49_B9.23") (pintype "bidirectional"))
    )
    (net (code "65") (name "/P9.24") (class "Default")
      (node (ref "BB.DISPLAY.CAPE-(BEAGLEBONE)") (pin "B9.24") (pinfunction "UART1.TXD_B9.24") (pintype "bidirectional"))
      (node (ref "BB.DISPLAY.CAPE-(CAPE)") (pin "B9.24") (pinfunction "UART1.TXD_B9.24") (pintype "bidirectional"))
    )
    (net (code "66") (name "/P9.25") (class "Default")
      (node (ref "BB.DISPLAY.CAPE-(BEAGLEBONE)") (pin "B9.25") (pinfunction "GPIO117_B9.25") (pintype "bidirectional"))
      (node (ref "BB.DISPLAY.CAPE-(CAPE)") (pin "B9.25") (pinfunction "GPIO117_B9.25") (pintype "bidirectional"))
    )
    (net (code "67") (name "/P9.26") (class "Default")
      (node (ref "BB.DISPLAY.CAPE-(BEAGLEBONE)") (pin "B9.26") (pinfunction "UART1.RXD_B9.26") (pintype "bidirectional"))
      (node (ref "BB.DISPLAY.CAPE-(CAPE)") (pin "B9.26") (pinfunction "UART1.RXD_B9.26") (pintype "bidirectional"))
    )
    (net (code "68") (name "/P9.27") (class "Default")
      (node (ref "BB.DISPLAY.CAPE-(BEAGLEBONE)") (pin "B9.27") (pinfunction "GPIO115_B9.27") (pintype "bidirectional"))
      (node (ref "BB.DISPLAY.CAPE-(CAPE)") (pin "B9.27") (pinfunction "GPIO115_B9.27") (pintype "bidirectional"))
    )
    (net (code "69") (name "/P9.28") (class "Default")
      (node (ref "BB.DISPLAY.CAPE-(BEAGLEBONE)") (pin "B9.28") (pinfunction "SPI1.CS0_B9.28") (pintype "bidirectional"))
      (node (ref "BB.DISPLAY.CAPE-(CAPE)") (pin "B9.28") (pinfunction "SPI1.CS0_B9.28") (pintype "bidirectional"))
    )
    (net (code "70") (name "/P9.29") (class "Default")
      (node (ref "BB.DISPLAY.CAPE-(BEAGLEBONE)") (pin "B9.29") (pinfunction "SPI1.D0_B9.29") (pintype "bidirectional"))
      (node (ref "BB.DISPLAY.CAPE-(CAPE)") (pin "B9.29") (pinfunction "SPI1.D0_B9.29") (pintype "bidirectional"))
    )
    (net (code "71") (name "/P9.31") (class "Default")
      (node (ref "BB.DISPLAY.CAPE-(BEAGLEBONE)") (pin "B9.31") (pinfunction "SPI1.SCK_B9.31") (pintype "bidirectional"))
      (node (ref "BB.DISPLAY.CAPE-(CAPE)") (pin "B9.31") (pinfunction "SPI1.SCK_B9.31") (pintype "bidirectional"))
    )
    (net (code "72") (name "/P9.32") (class "Default")
      (node (ref "BB.DISPLAY.CAPE-(BEAGLEBONE)") (pin "B9.32") (pinfunction "AVDD.ADC_B9.32") (pintype "bidirectional"))
      (node (ref "BB.DISPLAY.CAPE-(CAPE)") (pin "B9.32") (pinfunction "AVDD.ADC_B9.32") (pintype "bidirectional"))
    )
    (net (code "73") (name "/P9.33") (class "Default")
      (node (ref "BB.DISPLAY.CAPE-(BEAGLEBONE)") (pin "B9.33") (pinfunction "AIN4_B9.33") (pintype "bidirectional"))
      (node (ref "BB.DISPLAY.CAPE-(CAPE)") (pin "B9.33") (pinfunction "AIN4_B9.33") (pintype "bidirectional"))
    )
    (net (code "74") (name "/P9.34") (class "Default")
      (node (ref "BB.DISPLAY.CAPE-(BEAGLEBONE)") (pin "B9.34") (pinfunction "AGND.ADC_B9.34") (pintype "bidirectional"))
      (node (ref "BB.DISPLAY.CAPE-(CAPE)") (pin "B9.34") (pinfunction "AGND.ADC_B9.34") (pintype "bidirectional"))
    )
    (net (code "75") (name "/P9.35") (class "Default")
      (node (ref "BB.DISPLAY.CAPE-(BEAGLEBONE)") (pin "B9.35") (pinfunction "AIN6_B9.35") (pintype "bidirectional"))
      (node (ref "BB.DISPLAY.CAPE-(CAPE)") (pin "B9.35") (pinfunction "AIN6_B9.35") (pintype "bidirectional"))
    )
    (net (code "76") (name "/P9.36") (class "Default")
      (node (ref "BB.DISPLAY.CAPE-(BEAGLEBONE)") (pin "B9.36") (pinfunction "AIN5_B9.36") (pintype "bidirectional"))
      (node (ref "BB.DISPLAY.CAPE-(CAPE)") (pin "B9.36") (pinfunction "AIN5_B9.36") (pintype "bidirectional"))
    )
    (net (code "77") (name "/P9.37") (class "Default")
      (node (ref "BB.DISPLAY.CAPE-(BEAGLEBONE)") (pin "B9.37") (pinfunction "AIN2_B9.37") (pintype "bidirectional"))
      (node (ref "BB.DISPLAY.CAPE-(CAPE)") (pin "B9.37") (pinfunction "AIN2_B9.37") (pintype "bidirectional"))
    )
    (net (code "78") (name "/P9.38") (class "Default")
      (node (ref "BB.DISPLAY.CAPE-(BEAGLEBONE)") (pin "B9.38") (pinfunction "AIN3_B9.38") (pintype "bidirectional"))
      (node (ref "BB.DISPLAY.CAPE-(CAPE)") (pin "B9.38") (pinfunction "AIN3_B9.38") (pintype "bidirectional"))
    )
    (net (code "79") (name "/P9.39") (class "Default")
      (node (ref "BB.DISPLAY.CAPE-(BEAGLEBONE)") (pin "B9.39") (pinfunction "AIN0_B9.39") (pintype "bidirectional"))
      (node (ref "BB.DISPLAY.CAPE-(CAPE)") (pin "B9.39") (pinfunction "AIN0_B9.39") (pintype "bidirectional"))
    )
    (net (code "80") (name "/P9.40") (class "Default")
      (node (ref "BB.DISPLAY.CAPE-(BEAGLEBONE)") (pin "B9.40") (pinfunction "AIN1_B9.40") (pintype "bidirectional"))
      (node (ref "BB.DISPLAY.CAPE-(CAPE)") (pin "B9.40") (pinfunction "AIN1_B9.40") (pintype "bidirectional"))
    )
    (net (code "81") (name "/P9.41") (class "Default")
      (node (ref "BB.DISPLAY.CAPE-(BEAGLEBONE)") (pin "B9.41") (pinfunction "GPIO20_B9.41") (pintype "bidirectional"))
      (node (ref "BB.DISPLAY.CAPE-(CAPE)") (pin "B9.41") (pinfunction "GPIO20_B9.41") (pintype "bidirectional"))
    )
    (net (code "82") (name "/P9.42") (class "Default")
      (node (ref "BB.DISPLAY.CAPE-(BEAGLEBONE)") (pin "B9.42") (pinfunction "ECAPPWM0_B9.42") (pintype "bidirectional"))
      (node (ref "BB.DISPLAY.CAPE-(CAPE)") (pin "B9.42") (pinfunction "ECAPPWM0_B9.42") (pintype "bidirectional"))
    )
    (net (code "83") (name "/PUMP") (class "Default")
      (node (ref "D2") (pin "A") (pinfunction "ANODE_A") (pintype "bidirectional"))
      (node (ref "IC1") (pin "5") (pinfunction "SW_5") (pintype "bidirectional"))
      (node (ref "L2") (pin "2") (pinfunction "2_2") (pintype "bidirectional"))
    )
    (net (code "84") (name "/VDD.5V") (class "Default")
      (node (ref "BB.DISPLAY.CAPE-(BEAGLEBONE)") (pin "B9.5") (pinfunction "VDD.5V(1)_B9.5") (pintype "bidirectional"))
      (node (ref "BB.DISPLAY.CAPE-(BEAGLEBONE)") (pin "B9.6") (pinfunction "VDD.5V(2)_B9.6") (pintype "bidirectional"))
      (node (ref "BB.DISPLAY.CAPE-(CAPE)") (pin "B9.5") (pinfunction "VDD.5V(1)_B9.5") (pintype "bidirectional"))
      (node (ref "BB.DISPLAY.CAPE-(CAPE)") (pin "B9.6") (pinfunction "VDD.5V(2)_B9.6") (pintype "bidirectional"))
    )
    (net (code "85") (name "/WAKE") (class "Default")
      (node (ref "4.3") (pin "4") (pinfunction "4_4") (pintype "bidirectional"))
      (node (ref "5.0") (pin "4") (pinfunction "4_4") (pintype "bidirectional"))
      (node (ref "TP1") (pin "P$1") (pinfunction "TP_P$1") (pintype "bidirectional"))
    )
    (net (code "86") (name "GND") (class "Default")
      (node (ref "4.3") (pin "6") (pinfunction "6_6") (pintype "bidirectional"))
      (node (ref "5.0") (pin "6") (pinfunction "6_6") (pintype "bidirectional"))
      (node (ref "BB.DISPLAY.CAPE-(BEAGLEBONE)") (pin "B8.1") (pinfunction "DGND1_B8.1") (pintype "bidirectional"))
      (node (ref "BB.DISPLAY.CAPE-(BEAGLEBONE)") (pin "B8.2") (pinfunction "DGND2_B8.2") (pintype "bidirectional"))
      (node (ref "BB.DISPLAY.CAPE-(BEAGLEBONE)") (pin "B9.1") (pinfunction "DGND1_B9.1") (pintype "bidirectional"))
      (node (ref "BB.DISPLAY.CAPE-(BEAGLEBONE)") (pin "B9.2") (pinfunction "DGND2_B9.2") (pintype "bidirectional"))
      (node (ref "BB.DISPLAY.CAPE-(BEAGLEBONE)") (pin "B9.43") (pinfunction "DGND3_B9.43") (pintype "bidirectional"))
      (node (ref "BB.DISPLAY.CAPE-(BEAGLEBONE)") (pin "B9.44") (pinfunction "DGND4_B9.44") (pintype "bidirectional"))
      (node (ref "BB.DISPLAY.CAPE-(BEAGLEBONE)") (pin "B9.45") (pinfunction "DGND5_B9.45") (pintype "bidirectional"))
      (node (ref "BB.DISPLAY.CAPE-(BEAGLEBONE)") (pin "B9.46") (pinfunction "DGND6_B9.46") (pintype "bidirectional"))
      (node (ref "BB.DISPLAY.CAPE-(CAPE)") (pin "B8.1") (pinfunction "DGND1_B8.1") (pintype "bidirectional"))
      (node (ref "BB.DISPLAY.CAPE-(CAPE)") (pin "B8.2") (pinfunction "DGND2_B8.2") (pintype "bidirectional"))
      (node (ref "BB.DISPLAY.CAPE-(CAPE)") (pin "B9.1") (pinfunction "DGND1_B9.1") (pintype "bidirectional"))
      (node (ref "BB.DISPLAY.CAPE-(CAPE)") (pin "B9.2") (pinfunction "DGND2_B9.2") (pintype "bidirectional"))
      (node (ref "BB.DISPLAY.CAPE-(CAPE)") (pin "B9.43") (pinfunction "DGND3_B9.43") (pintype "bidirectional"))
      (node (ref "BB.DISPLAY.CAPE-(CAPE)") (pin "B9.44") (pinfunction "DGND4_B9.44") (pintype "bidirectional"))
      (node (ref "BB.DISPLAY.CAPE-(CAPE)") (pin "B9.45") (pinfunction "DGND5_B9.45") (pintype "bidirectional"))
      (node (ref "BB.DISPLAY.CAPE-(CAPE)") (pin "B9.46") (pinfunction "DGND6_B9.46") (pintype "bidirectional"))
      (node (ref "C1") (pin "2") (pinfunction "2_2") (pintype "passive"))
      (node (ref "C2") (pin "2") (pinfunction "2_2") (pintype "passive"))
      (node (ref "C3") (pin "2") (pinfunction "2_2") (pintype "passive"))
      (node (ref "C4") (pin "2") (pinfunction "2_2") (pintype "passive"))
      (node (ref "C5") (pin "2") (pinfunction "2_2") (pintype "bidirectional"))
      (node (ref "C6") (pin "2") (pinfunction "2_2") (pintype "passive"))
      (node (ref "C7") (pin "2") (pinfunction "2_2") (pintype "bidirectional"))
      (node (ref "C8") (pin "2") (pinfunction "2_2") (pintype "bidirectional"))
      (node (ref "C9") (pin "2") (pinfunction "2_2") (pintype "bidirectional"))
      (node (ref "IC1") (pin "2") (pinfunction "GND_2") (pintype "bidirectional"))
      (node (ref "IC1") (pin "THERMAL") (pinfunction "GND_THERMAL") (pintype "bidirectional"))
      (node (ref "IC2") (pin "2") (pinfunction "GND_2") (pintype "bidirectional"))
      (node (ref "IC3") (pin "4") (pinfunction "VSS_4") (pintype "bidirectional"))
      (node (ref "JMP1") (pin "2") (pinfunction "2_2") (pintype "bidirectional"))
      (node (ref "R1") (pin "2") (pinfunction "2_2") (pintype "passive"))
      (node (ref "R2") (pin "2") (pinfunction "2_2") (pintype "passive"))
      (node (ref "SJ1") (pin "1") (pinfunction "1_1") (pintype "bidirectional"))
      (node (ref "SJ2") (pin "1") (pinfunction "1_1") (pintype "bidirectional"))
      (node (ref "X2") (pin "13") (pinfunction "GND(G0)_13") (pintype "bidirectional"))
      (node (ref "X2") (pin "14") (pinfunction "GND(G1)_14") (pintype "bidirectional"))
      (node (ref "X2") (pin "21") (pinfunction "(B0)GND_21") (pintype "bidirectional"))
      (node (ref "X2") (pin "22") (pinfunction "(B1)GND_22") (pintype "bidirectional"))
      (node (ref "X2") (pin "23") (pinfunction "(B2)GND_23") (pintype "bidirectional"))
      (node (ref "X2") (pin "29") (pinfunction "GND2_29") (pintype "bidirectional"))
      (node (ref "X2") (pin "3") (pinfunction "GND1_3") (pintype "bidirectional"))
      (node (ref "X2") (pin "36") (pinfunction "GND3_36") (pintype "bidirectional"))
      (node (ref "X2") (pin "5") (pinfunction "GND(R0)_5") (pintype "bidirectional"))
      (node (ref "X2") (pin "6") (pinfunction "GND(R1)_6") (pintype "bidirectional"))
      (node (ref "X2") (pin "7") (pinfunction "GND(R2)_7") (pintype "bidirectional"))
    )
    (net (code "87") (name "Net-(IC3-A0)") (class "Default")
      (node (ref "IC3") (pin "1") (pinfunction "A0_1") (pintype "bidirectional"))
      (node (ref "R3") (pin "2") (pinfunction "2_2") (pintype "bidirectional"))
      (node (ref "SJ1") (pin "2") (pinfunction "2_2") (pintype "bidirectional"))
    )
    (net (code "88") (name "Net-(IC3-A1)") (class "Default")
      (node (ref "IC3") (pin "2") (pinfunction "A1_2") (pintype "bidirectional"))
      (node (ref "R4") (pin "2") (pinfunction "2_2") (pintype "bidirectional"))
      (node (ref "SJ2") (pin "2") (pinfunction "2_2") (pintype "bidirectional"))
    )
    (net (code "89") (name "Net-(IC3-A2)") (class "Default")
      (node (ref "IC3") (pin "3") (pinfunction "A2_3") (pintype "bidirectional"))
      (node (ref "R5") (pin "2") (pinfunction "2_2") (pintype "bidirectional"))
    )
    (net (code "90") (name "Net-(IC3-WP)") (class "Default")
      (node (ref "IC3") (pin "7") (pinfunction "WP_7") (pintype "bidirectional"))
      (node (ref "JMP1") (pin "1") (pinfunction "1_1") (pintype "bidirectional"))
      (node (ref "R6") (pin "1") (pinfunction "1_1") (pintype "bidirectional"))
    )
    (net (code "91") (name "VCC") (class "Default")
      (node (ref "4.3") (pin "3") (pinfunction "3_3") (pintype "bidirectional"))
      (node (ref "5.0") (pin "3") (pinfunction "3_3") (pintype "bidirectional"))
      (node (ref "BB.DISPLAY.CAPE-(BEAGLEBONE)") (pin "B9.3") (pinfunction "VDD.3V3(1)_B9.3") (pintype "bidirectional"))
      (node (ref "BB.DISPLAY.CAPE-(BEAGLEBONE)") (pin "B9.4") (pinfunction "VDD.3V3(2)_B9.4") (pintype "bidirectional"))
      (node (ref "BB.DISPLAY.CAPE-(CAPE)") (pin "B9.3") (pinfunction "VDD.3V3(1)_B9.3") (pintype "bidirectional"))
      (node (ref "BB.DISPLAY.CAPE-(CAPE)") (pin "B9.4") (pinfunction "VDD.3V3(2)_B9.4") (pintype "bidirectional"))
      (node (ref "C3") (pin "1") (pinfunction "1_1") (pintype "passive"))
      (node (ref "C4") (pin "1") (pinfunction "1_1") (pintype "passive"))
      (node (ref "C7") (pin "1") (pinfunction "1_1") (pintype "bidirectional"))
      (node (ref "C8") (pin "1") (pinfunction "1_1") (pintype "bidirectional"))
      (node (ref "C9") (pin "1") (pinfunction "1_1") (pintype "bidirectional"))
      (node (ref "IC3") (pin "8") (pinfunction "VCC_8") (pintype "bidirectional"))
      (node (ref "R3") (pin "1") (pinfunction "1_1") (pintype "bidirectional"))
      (node (ref "R4") (pin "1") (pinfunction "1_1") (pintype "bidirectional"))
      (node (ref "R5") (pin "1") (pinfunction "1_1") (pintype "bidirectional"))
      (node (ref "R6") (pin "2") (pinfunction "2_2") (pintype "bidirectional"))
      (node (ref "R7") (pin "2") (pinfunction "2_2") (pintype "bidirectional"))
      (node (ref "R8") (pin "2") (pinfunction "2_2") (pintype "bidirectional"))
      (node (ref "X2") (pin "31") (pinfunction "DISP_31") (pintype "bidirectional"))
      (node (ref "X2") (pin "4") (pinfunction "VDD1_4") (pintype "bidirectional"))
    )
    (net (code "92") (name "unconnected-(FUD1-PadP$1)") (class "Default")
      (node (ref "FUD1") (pin "P$1") (pinfunction "P$1_P$1") (pintype "no_connect"))
    )
    (net (code "93") (name "unconnected-(FUD2-PadP$1)") (class "Default")
      (node (ref "FUD2") (pin "P$1") (pinfunction "P$1_P$1") (pintype "no_connect"))
    )
    (net (code "94") (name "unconnected-(FUD3-PadP$1)") (class "Default")
      (node (ref "FUD3") (pin "P$1") (pinfunction "P$1_P$1") (pintype "no_connect"))
    )
    (net (code "95") (name "unconnected-(X2-(NC)T.XL-Pad39)") (class "Default")
      (node (ref "X2") (pin "39") (pinfunction "(NC)T.XL_39") (pintype "bidirectional"))
    )
    (net (code "96") (name "unconnected-(X2-(NC)T.XR-Pad37)") (class "Default")
      (node (ref "X2") (pin "37") (pinfunction "(NC)T.XR_37") (pintype "bidirectional"))
    )
    (net (code "97") (name "unconnected-(X2-(NC)T.YD-Pad38)") (class "Default")
      (node (ref "X2") (pin "38") (pinfunction "(NC)T.YD_38") (pintype "bidirectional"))
    )
    (net (code "98") (name "unconnected-(X2-(NC)T.YU-Pad40)") (class "Default")
      (node (ref "X2") (pin "40") (pinfunction "(NC)T.YU_40") (pintype "bidirectional"))
    )
    (net (code "99") (name "unconnected-(X2-NC1-Pad35)") (class "Default")
      (node (ref "X2") (pin "35") (pinfunction "NC1_35") (pintype "bidirectional"))
    )
  )
)
